# Digit.net
KiCad netlist of a schematic drawn in Altium Designer
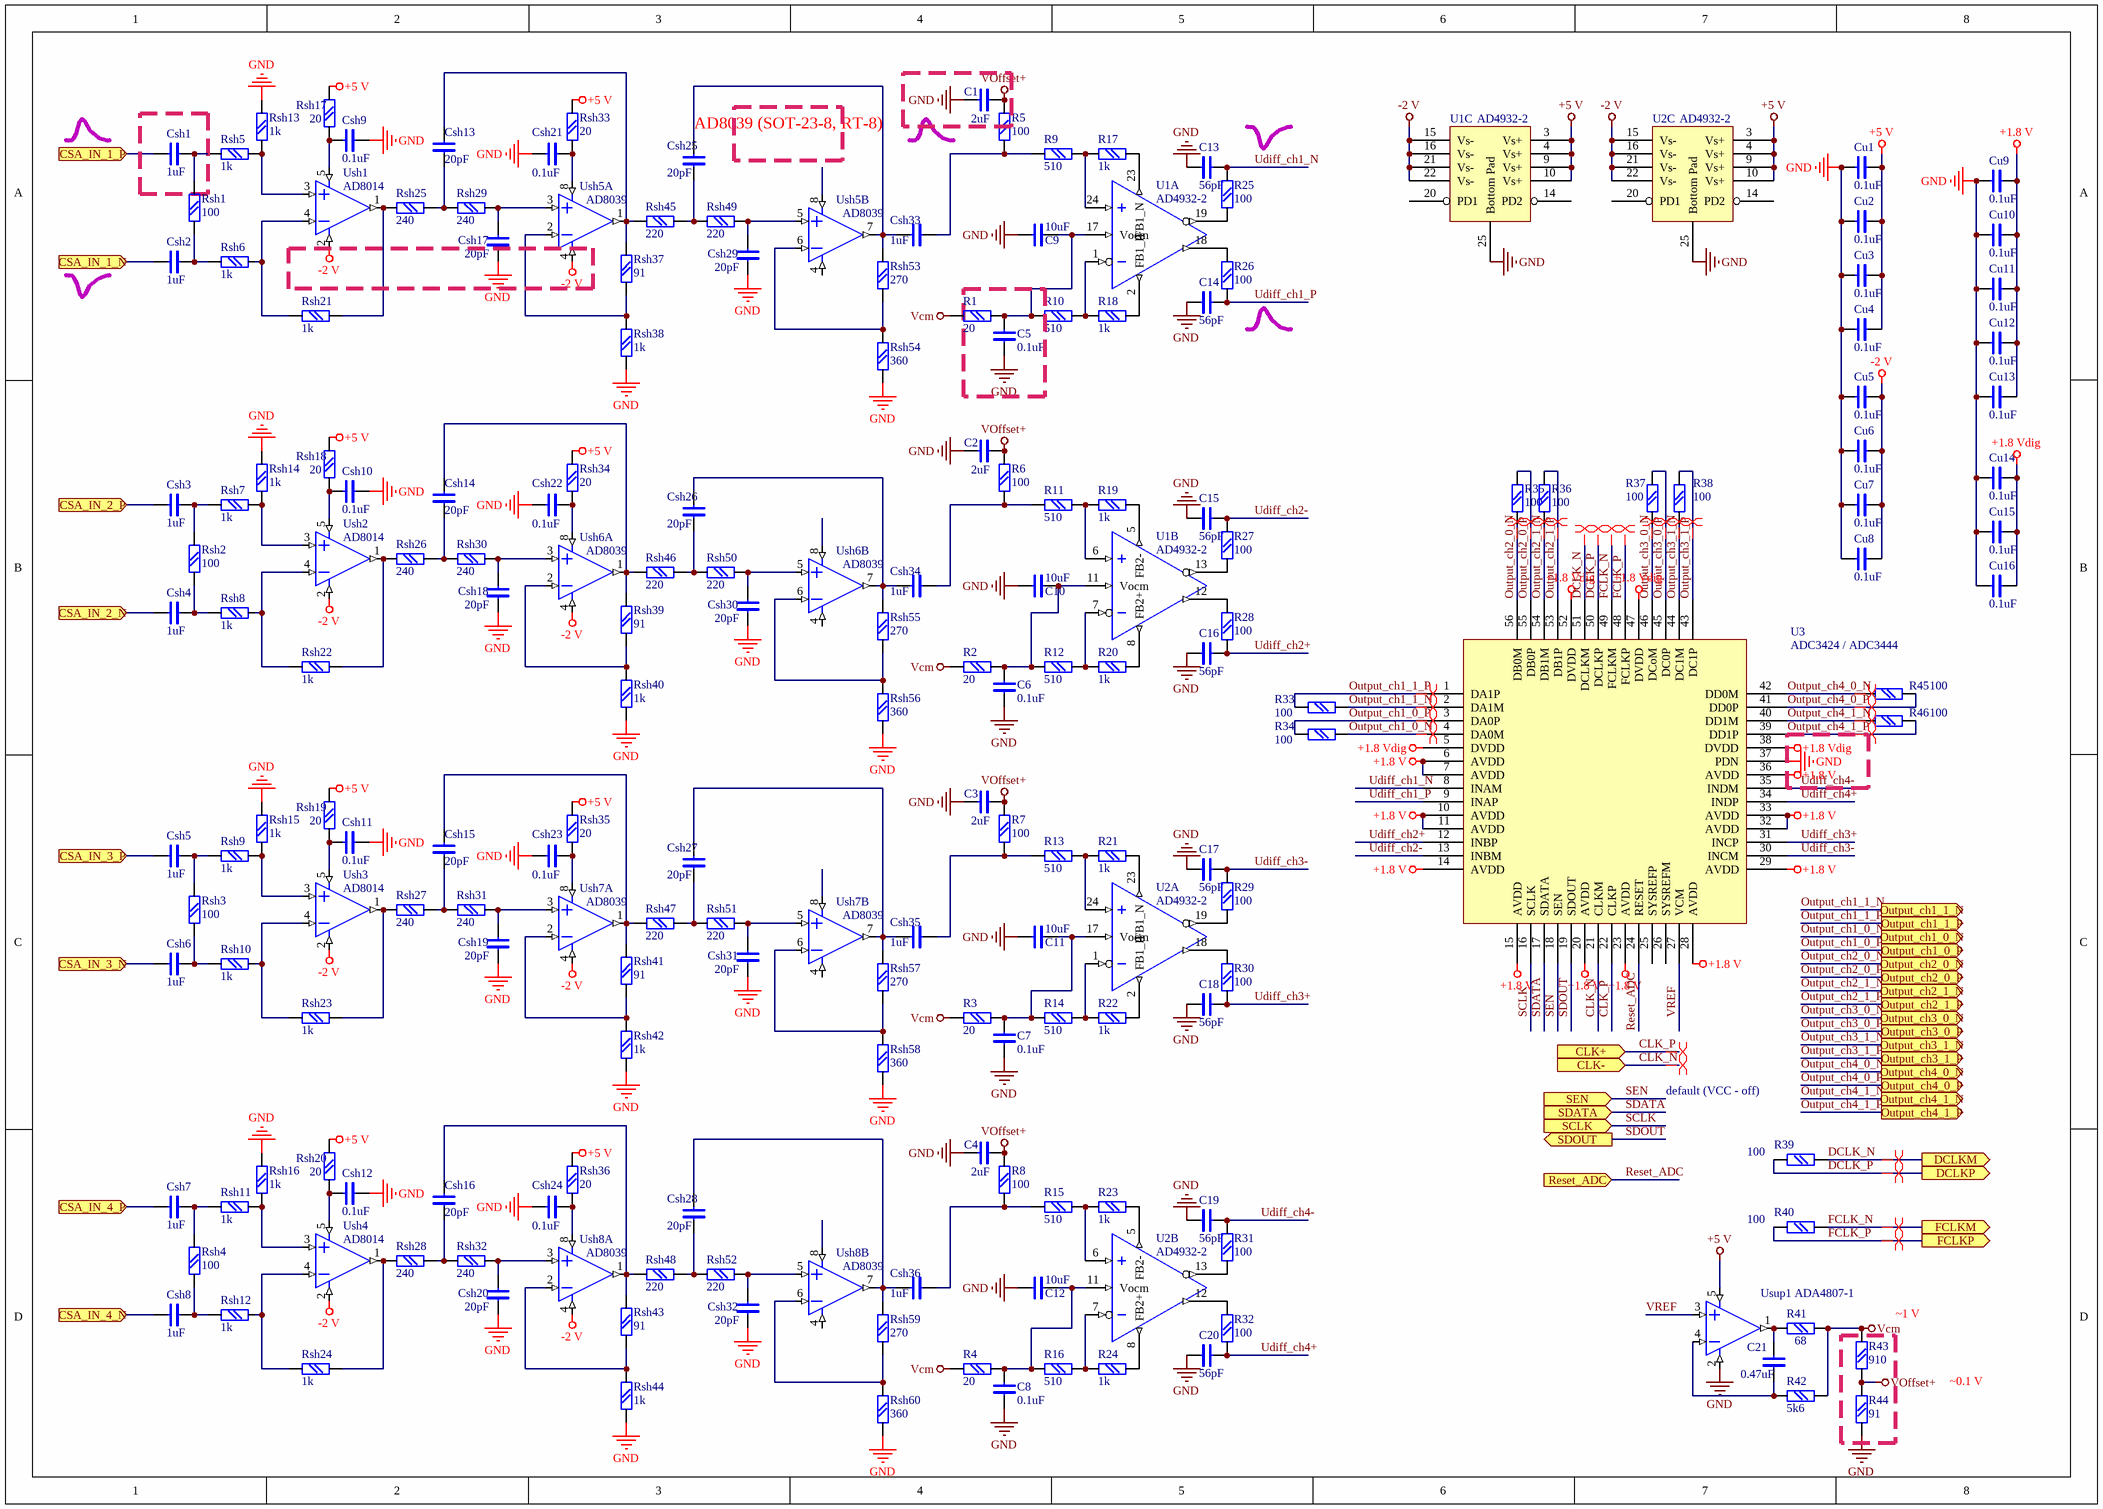
[diagram p0: Digit.SchDoc]

(export (version "E")
  (design (tool "Eeschema 10.0.6"))
  (components
    (comp (ref "C1") (value "2uF") (footprint "chip0603") (libsource (lib "vDevice") (part "C")))
    (comp (ref "C2") (value "2uF") (footprint "chip0603") (libsource (lib "vDevice") (part "C")))
    (comp (ref "C3") (value "2uF") (footprint "chip0603") (libsource (lib "vDevice") (part "C")))
    (comp (ref "C4") (value "2uF") (footprint "chip0603") (libsource (lib "vDevice") (part "C")))
    (comp (ref "C5") (value "0.1uF") (footprint "chip0603") (libsource (lib "vDevice") (part "C")))
    (comp (ref "C6") (value "0.1uF") (footprint "chip0603") (libsource (lib "vDevice") (part "C")))
    (comp (ref "C7") (value "0.1uF") (footprint "chip0603") (libsource (lib "vDevice") (part "C")))
    (comp (ref "C8") (value "0.1uF") (footprint "chip0603") (libsource (lib "vDevice") (part "C")))
    (comp (ref "C9") (value "10uF") (footprint "chip0603") (libsource (lib "vDevice") (part "C")))
    (comp (ref "C10") (value "10uF") (footprint "chip0603") (libsource (lib "vDevice") (part "C")))
    (comp (ref "C11") (value "10uF") (footprint "chip0603") (libsource (lib "vDevice") (part "C")))
    (comp (ref "C12") (value "10uF") (footprint "chip0603") (libsource (lib "vDevice") (part "C")))
    (comp (ref "C13") (value "56pF") (footprint "chip0603") (libsource (lib "vDevice") (part "C")))
    (comp (ref "C14") (value "56pF") (footprint "chip0603") (libsource (lib "vDevice") (part "C")))
    (comp (ref "C15") (value "56pF") (footprint "chip0603") (libsource (lib "vDevice") (part "C")))
    (comp (ref "C16") (value "56pF") (footprint "chip0603") (libsource (lib "vDevice") (part "C")))
    (comp (ref "C17") (value "56pF") (footprint "chip0603") (libsource (lib "vDevice") (part "C")))
    (comp (ref "C18") (value "56pF") (footprint "chip0603") (libsource (lib "vDevice") (part "C")))
    (comp (ref "C19") (value "56pF") (footprint "chip0603") (libsource (lib "vDevice") (part "C")))
    (comp (ref "C20") (value "56pF") (footprint "chip0603") (libsource (lib "vDevice") (part "C")))
    (comp (ref "C21") (value "0.47uF") (footprint "chip0603") (libsource (lib "*") (part "C")))
    (comp (ref "Csh1") (value "1uF") (footprint "chip0603") (libsource (lib "*") (part "C")))
    (comp (ref "Csh2") (value "1uF") (footprint "chip0603") (libsource (lib "*") (part "C")))
    (comp (ref "Csh3") (value "1uF") (footprint "chip0603") (libsource (lib "*") (part "C")))
    (comp (ref "Csh4") (value "1uF") (footprint "chip0603") (libsource (lib "*") (part "C")))
    (comp (ref "Csh5") (value "1uF") (footprint "chip0603") (libsource (lib "*") (part "C")))
    (comp (ref "Csh6") (value "1uF") (footprint "chip0603") (libsource (lib "*") (part "C")))
    (comp (ref "Csh7") (value "1uF") (footprint "chip0603") (libsource (lib "*") (part "C")))
    (comp (ref "Csh8") (value "1uF") (footprint "chip0603") (libsource (lib "*") (part "C")))
    (comp (ref "Csh9") (value "0.1uF") (footprint "chip0603") (libsource (lib "*") (part "C")))
    (comp (ref "Csh10") (value "0.1uF") (footprint "chip0603") (libsource (lib "*") (part "C")))
    (comp (ref "Csh11") (value "0.1uF") (footprint "chip0603") (libsource (lib "*") (part "C")))
    (comp (ref "Csh12") (value "0.1uF") (footprint "chip0603") (libsource (lib "*") (part "C")))
    (comp (ref "Csh13") (value "20pF") (footprint "chip0603") (libsource (lib "*") (part "C")))
    (comp (ref "Csh14") (value "20pF") (footprint "chip0603") (libsource (lib "*") (part "C")))
    (comp (ref "Csh15") (value "20pF") (footprint "chip0603") (libsource (lib "*") (part "C")))
    (comp (ref "Csh16") (value "20pF") (footprint "chip0603") (libsource (lib "*") (part "C")))
    (comp (ref "Csh17") (value "20pF") (footprint "chip0603") (libsource (lib "*") (part "C")))
    (comp (ref "Csh18") (value "20pF") (footprint "chip0603") (libsource (lib "*") (part "C")))
    (comp (ref "Csh19") (value "20pF") (footprint "chip0603") (libsource (lib "*") (part "C")))
    (comp (ref "Csh20") (value "20pF") (footprint "chip0603") (libsource (lib "*") (part "C")))
    (comp (ref "Csh21") (value "0.1uF") (footprint "chip0603") (libsource (lib "*") (part "C")))
    (comp (ref "Csh22") (value "0.1uF") (footprint "chip0603") (libsource (lib "*") (part "C")))
    (comp (ref "Csh23") (value "0.1uF") (footprint "chip0603") (libsource (lib "*") (part "C")))
    (comp (ref "Csh24") (value "0.1uF") (footprint "chip0603") (libsource (lib "*") (part "C")))
    (comp (ref "Csh25") (value "20pF") (footprint "chip0603") (libsource (lib "*") (part "C")))
    (comp (ref "Csh26") (value "20pF") (footprint "chip0603") (libsource (lib "*") (part "C")))
    (comp (ref "Csh27") (value "20pF") (footprint "chip0603") (libsource (lib "*") (part "C")))
    (comp (ref "Csh28") (value "20pF") (footprint "chip0603") (libsource (lib "*") (part "C")))
    (comp (ref "Csh29") (value "20pF") (footprint "chip0603") (libsource (lib "*") (part "C")))
    (comp (ref "Csh30") (value "20pF") (footprint "chip0603") (libsource (lib "*") (part "C")))
    (comp (ref "Csh31") (value "20pF") (footprint "chip0603") (libsource (lib "*") (part "C")))
    (comp (ref "Csh32") (value "20pF") (footprint "chip0603") (libsource (lib "*") (part "C")))
    (comp (ref "Csh33") (value "1uF") (footprint "chip0603") (libsource (lib "*") (part "C")))
    (comp (ref "Csh34") (value "1uF") (footprint "chip0603") (libsource (lib "*") (part "C")))
    (comp (ref "Csh35") (value "1uF") (footprint "chip0603") (libsource (lib "*") (part "C")))
    (comp (ref "Csh36") (value "1uF") (footprint "chip0603") (libsource (lib "*") (part "C")))
    (comp (ref "Cu1") (value "0.1uF") (footprint "chip0603") (libsource (lib "*") (part "C")))
    (comp (ref "Cu2") (value "0.1uF") (footprint "chip0603") (libsource (lib "*") (part "C")))
    (comp (ref "Cu3") (value "0.1uF") (footprint "chip0603") (libsource (lib "*") (part "C")))
    (comp (ref "Cu4") (value "0.1uF") (footprint "chip0603") (libsource (lib "*") (part "C")))
    (comp (ref "Cu5") (value "0.1uF") (footprint "chip0603") (libsource (lib "*") (part "C")))
    (comp (ref "Cu6") (value "0.1uF") (footprint "chip0603") (libsource (lib "*") (part "C")))
    (comp (ref "Cu7") (value "0.1uF") (footprint "chip0603") (libsource (lib "*") (part "C")))
    (comp (ref "Cu8") (value "0.1uF") (footprint "chip0603") (libsource (lib "*") (part "C")))
    (comp (ref "Cu9") (value "0.1uF") (footprint "chip0603") (libsource (lib "*") (part "C")))
    (comp (ref "Cu10") (value "0.1uF") (footprint "chip0603") (libsource (lib "*") (part "C")))
    (comp (ref "Cu11") (value "0.1uF") (footprint "chip0603") (libsource (lib "*") (part "C")))
    (comp (ref "Cu12") (value "0.1uF") (footprint "chip0603") (libsource (lib "*") (part "C")))
    (comp (ref "Cu13") (value "0.1uF") (footprint "chip0603") (libsource (lib "*") (part "C")))
    (comp (ref "Cu14") (value "0.1uF") (footprint "chip0603") (libsource (lib "*") (part "C")))
    (comp (ref "Cu15") (value "0.1uF") (footprint "chip0603") (libsource (lib "*") (part "C")))
    (comp (ref "Cu16") (value "0.1uF") (footprint "chip0603") (libsource (lib "*") (part "C")))
    (comp (ref "R1") (value "20") (footprint "chip0603") (libsource (lib "vDevice") (part "R")))
    (comp (ref "R2") (value "20") (footprint "chip0603") (libsource (lib "vDevice") (part "R")))
    (comp (ref "R3") (value "20") (footprint "chip0603") (libsource (lib "vDevice") (part "R")))
    (comp (ref "R4") (value "20") (footprint "chip0603") (libsource (lib "vDevice") (part "R")))
    (comp (ref "R5") (value "100") (footprint "chip0603") (libsource (lib "vDevice") (part "R")))
    (comp (ref "R6") (value "100") (footprint "chip0603") (libsource (lib "vDevice") (part "R")))
    (comp (ref "R7") (value "100") (footprint "chip0603") (libsource (lib "vDevice") (part "R")))
    (comp (ref "R8") (value "100") (footprint "chip0603") (libsource (lib "vDevice") (part "R")))
    (comp (ref "R9") (value "510") (footprint "chip0603") (libsource (lib "vDevice") (part "R")))
    (comp (ref "R10") (value "510") (footprint "chip0603") (libsource (lib "vDevice") (part "R")))
    (comp (ref "R11") (value "510") (footprint "chip0603") (libsource (lib "vDevice") (part "R")))
    (comp (ref "R12") (value "510") (footprint "chip0603") (libsource (lib "vDevice") (part "R")))
    (comp (ref "R13") (value "510") (footprint "chip0603") (libsource (lib "vDevice") (part "R")))
    (comp (ref "R14") (value "510") (footprint "chip0603") (libsource (lib "vDevice") (part "R")))
    (comp (ref "R15") (value "510") (footprint "chip0603") (libsource (lib "vDevice") (part "R")))
    (comp (ref "R16") (value "510") (footprint "chip0603") (libsource (lib "vDevice") (part "R")))
    (comp (ref "R17") (value "1k") (footprint "chip0603") (libsource (lib "vDevice") (part "R")))
    (comp (ref "R18") (value "1k") (footprint "chip0603") (libsource (lib "vDevice") (part "R")))
    (comp (ref "R19") (value "1k") (footprint "chip0603") (libsource (lib "vDevice") (part "R")))
    (comp (ref "R20") (value "1k") (footprint "chip0603") (libsource (lib "vDevice") (part "R")))
    (comp (ref "R21") (value "1k") (footprint "chip0603") (libsource (lib "vDevice") (part "R")))
    (comp (ref "R22") (value "1k") (footprint "chip0603") (libsource (lib "vDevice") (part "R")))
    (comp (ref "R23") (value "1k") (footprint "chip0603") (libsource (lib "vDevice") (part "R")))
    (comp (ref "R24") (value "1k") (footprint "chip0603") (libsource (lib "vDevice") (part "R")))
    (comp (ref "R25") (value "100") (footprint "chip0603") (libsource (lib "vDevice") (part "R")))
    (comp (ref "R26") (value "100") (footprint "chip0603") (libsource (lib "vDevice") (part "R")))
    (comp (ref "R27") (value "100") (footprint "chip0603") (libsource (lib "vDevice") (part "R")))
    (comp (ref "R28") (value "100") (footprint "chip0603") (libsource (lib "vDevice") (part "R")))
    (comp (ref "R29") (value "100") (footprint "chip0603") (libsource (lib "vDevice") (part "R")))
    (comp (ref "R30") (value "100") (footprint "chip0603") (libsource (lib "vDevice") (part "R")))
    (comp (ref "R31") (value "100") (footprint "chip0603") (libsource (lib "vDevice") (part "R")))
    (comp (ref "R32") (value "100") (footprint "chip0603") (libsource (lib "vDevice") (part "R")))
    (comp (ref "R33") (value "100") (footprint "0402") (libsource (lib "vDevice") (part "R")))
    (comp (ref "R34") (value "100") (footprint "0402") (libsource (lib "vDevice") (part "R")))
    (comp (ref "R35") (value "100") (footprint "0402") (libsource (lib "vDevice") (part "R")))
    (comp (ref "R36") (value "100") (footprint "0402") (libsource (lib "vDevice") (part "R")))
    (comp (ref "R37") (value "100") (footprint "0402") (libsource (lib "vDevice") (part "R")))
    (comp (ref "R38") (value "100") (footprint "0402") (libsource (lib "vDevice") (part "R")))
    (comp (ref "R39") (value "100") (footprint "0402") (libsource (lib "vDevice") (part "R")))
    (comp (ref "R40") (value "100") (footprint "0402") (libsource (lib "vDevice") (part "R")))
    (comp (ref "R41") (value "68") (footprint "chip0603") (libsource (lib "vDevice") (part "R")))
    (comp (ref "R42") (value "5k6") (footprint "chip0603") (libsource (lib "vDevice") (part "R")))
    (comp (ref "R43") (value "910") (footprint "chip0603") (libsource (lib "vDevice") (part "R")))
    (comp (ref "R44") (value "91") (footprint "chip0603") (libsource (lib "vDevice") (part "R")))
    (comp (ref "R45") (value "100") (footprint "0402") (libsource (lib "vDevice") (part "R")))
    (comp (ref "R46") (value "100") (footprint "0402") (libsource (lib "vDevice") (part "R")))
    (comp (ref "Rsh1") (value "100") (footprint "chip0603") (libsource (lib "vDevice") (part "R")))
    (comp (ref "Rsh2") (value "100") (footprint "chip0603") (libsource (lib "vDevice") (part "R")))
    (comp (ref "Rsh3") (value "100") (footprint "chip0603") (libsource (lib "vDevice") (part "R")))
    (comp (ref "Rsh4") (value "100") (footprint "chip0603") (libsource (lib "vDevice") (part "R")))
    (comp (ref "Rsh5") (value "1k") (footprint "chip0603") (libsource (lib "vDevice") (part "R")))
    (comp (ref "Rsh6") (value "1k") (footprint "chip0603") (libsource (lib "vDevice") (part "R")))
    (comp (ref "Rsh7") (value "1k") (footprint "chip0603") (libsource (lib "vDevice") (part "R")))
    (comp (ref "Rsh8") (value "1k") (footprint "chip0603") (libsource (lib "vDevice") (part "R")))
    (comp (ref "Rsh9") (value "1k") (footprint "chip0603") (libsource (lib "vDevice") (part "R")))
    (comp (ref "Rsh10") (value "1k") (footprint "chip0603") (libsource (lib "vDevice") (part "R")))
    (comp (ref "Rsh11") (value "1k") (footprint "chip0603") (libsource (lib "vDevice") (part "R")))
    (comp (ref "Rsh12") (value "1k") (footprint "chip0603") (libsource (lib "vDevice") (part "R")))
    (comp (ref "Rsh13") (value "1k") (footprint "chip0603") (libsource (lib "vDevice") (part "R")))
    (comp (ref "Rsh14") (value "1k") (footprint "chip0603") (libsource (lib "vDevice") (part "R")))
    (comp (ref "Rsh15") (value "1k") (footprint "chip0603") (libsource (lib "vDevice") (part "R")))
    (comp (ref "Rsh16") (value "1k") (footprint "chip0603") (libsource (lib "vDevice") (part "R")))
    (comp (ref "Rsh17") (value "20") (footprint "chip0603") (libsource (lib "*") (part "R")))
    (comp (ref "Rsh18") (value "20") (footprint "chip0603") (libsource (lib "*") (part "R")))
    (comp (ref "Rsh19") (value "20") (footprint "chip0603") (libsource (lib "*") (part "R")))
    (comp (ref "Rsh20") (value "20") (footprint "chip0603") (libsource (lib "*") (part "R")))
    (comp (ref "Rsh21") (value "1k") (footprint "chip0603") (libsource (lib "vDevice") (part "R")))
    (comp (ref "Rsh22") (value "1k") (footprint "chip0603") (libsource (lib "vDevice") (part "R")))
    (comp (ref "Rsh23") (value "1k") (footprint "chip0603") (libsource (lib "vDevice") (part "R")))
    (comp (ref "Rsh24") (value "1k") (footprint "chip0603") (libsource (lib "vDevice") (part "R")))
    (comp (ref "Rsh25") (value "240") (footprint "chip0603") (libsource (lib "vDevice") (part "R")))
    (comp (ref "Rsh26") (value "240") (footprint "chip0603") (libsource (lib "vDevice") (part "R")))
    (comp (ref "Rsh27") (value "240") (footprint "chip0603") (libsource (lib "vDevice") (part "R")))
    (comp (ref "Rsh28") (value "240") (footprint "chip0603") (libsource (lib "vDevice") (part "R")))
    (comp (ref "Rsh29") (value "240") (footprint "chip0603") (libsource (lib "vDevice") (part "R")))
    (comp (ref "Rsh30") (value "240") (footprint "chip0603") (libsource (lib "vDevice") (part "R")))
    (comp (ref "Rsh31") (value "240") (footprint "chip0603") (libsource (lib "vDevice") (part "R")))
    (comp (ref "Rsh32") (value "240") (footprint "chip0603") (libsource (lib "vDevice") (part "R")))
    (comp (ref "Rsh33") (value "20") (footprint "chip0603") (libsource (lib "*") (part "R")))
    (comp (ref "Rsh34") (value "20") (footprint "chip0603") (libsource (lib "*") (part "R")))
    (comp (ref "Rsh35") (value "20") (footprint "chip0603") (libsource (lib "*") (part "R")))
    (comp (ref "Rsh36") (value "20") (footprint "chip0603") (libsource (lib "*") (part "R")))
    (comp (ref "Rsh37") (value "91") (footprint "chip0603") (libsource (lib "vDevice") (part "R")))
    (comp (ref "Rsh38") (value "1k") (footprint "chip0603") (libsource (lib "vDevice") (part "R")))
    (comp (ref "Rsh39") (value "91") (footprint "chip0603") (libsource (lib "vDevice") (part "R")))
    (comp (ref "Rsh40") (value "1k") (footprint "chip0603") (libsource (lib "vDevice") (part "R")))
    (comp (ref "Rsh41") (value "91") (footprint "chip0603") (libsource (lib "vDevice") (part "R")))
    (comp (ref "Rsh42") (value "1k") (footprint "chip0603") (libsource (lib "vDevice") (part "R")))
    (comp (ref "Rsh43") (value "91") (footprint "chip0603") (libsource (lib "vDevice") (part "R")))
    (comp (ref "Rsh44") (value "1k") (footprint "chip0603") (libsource (lib "vDevice") (part "R")))
    (comp (ref "Rsh45") (value "220") (footprint "chip0603") (libsource (lib "vDevice") (part "R")))
    (comp (ref "Rsh46") (value "220") (footprint "chip0603") (libsource (lib "vDevice") (part "R")))
    (comp (ref "Rsh47") (value "220") (footprint "chip0603") (libsource (lib "vDevice") (part "R")))
    (comp (ref "Rsh48") (value "220") (footprint "chip0603") (libsource (lib "vDevice") (part "R")))
    (comp (ref "Rsh49") (value "220") (footprint "chip0603") (libsource (lib "vDevice") (part "R")))
    (comp (ref "Rsh50") (value "220") (footprint "chip0603") (libsource (lib "vDevice") (part "R")))
    (comp (ref "Rsh51") (value "220") (footprint "chip0603") (libsource (lib "vDevice") (part "R")))
    (comp (ref "Rsh52") (value "220") (footprint "chip0603") (libsource (lib "vDevice") (part "R")))
    (comp (ref "Rsh53") (value "270") (footprint "chip0603") (libsource (lib "vDevice") (part "R")))
    (comp (ref "Rsh54") (value "360") (footprint "chip0603") (libsource (lib "vDevice") (part "R")))
    (comp (ref "Rsh55") (value "270") (footprint "chip0603") (libsource (lib "vDevice") (part "R")))
    (comp (ref "Rsh56") (value "360") (footprint "chip0603") (libsource (lib "vDevice") (part "R")))
    (comp (ref "Rsh57") (value "270") (footprint "chip0603") (libsource (lib "vDevice") (part "R")))
    (comp (ref "Rsh58") (value "360") (footprint "chip0603") (libsource (lib "vDevice") (part "R")))
    (comp (ref "Rsh59") (value "270") (footprint "chip0603") (libsource (lib "vDevice") (part "R")))
    (comp (ref "Rsh60") (value "360") (footprint "chip0603") (libsource (lib "vDevice") (part "R")))
    (comp (ref "U1") (value "AD4932-2") (footprint "CP-24-13") (libsource (lib "") (part "AD4932-2_1")))
    (comp (ref "U2") (value "AD4932-2") (footprint "CP-24-13") (libsource (lib "") (part "AD4932-2_1")))
    (comp (ref "U3")
      (value "ADC3424 / ADC3444")
      (footprint "PQFN-56")
      (libsource (lib "Backup of Mylib") (part "ADC3424"))
    )
    (comp (ref "Ush1") (value "AD8014") (footprint "RT-5") (libsource (lib "vAnalog") (part "AD8005ART")))
    (comp (ref "Ush2") (value "AD8014") (footprint "RT-5") (libsource (lib "vAnalog") (part "AD8005ART")))
    (comp (ref "Ush3") (value "AD8014") (footprint "RT-5") (libsource (lib "vAnalog") (part "AD8005ART")))
    (comp (ref "Ush4") (value "AD8014") (footprint "RT-5") (libsource (lib "vAnalog") (part "AD8005ART")))
    (comp (ref "Ush5") (value "AD8039") (footprint "SOT23-8") (libsource (lib "vAnalog") (part "AD8008")))
    (comp (ref "Ush6") (value "AD8039") (footprint "SOT23-8") (libsource (lib "vAnalog") (part "AD8008")))
    (comp (ref "Ush7") (value "AD8039") (footprint "SOT23-8") (libsource (lib "vAnalog") (part "AD8008")))
    (comp (ref "Ush8") (value "AD8039") (footprint "SOT23-8") (libsource (lib "vAnalog") (part "AD8008")))
    (comp (ref "Usup1")
      (value "ADA4807-1")
      (footprint "SOT23-5")
      (libsource (lib "vAnalog") (part "AD8005ART"))
    )
  )
  (nets
    (net (code "1") (name "+1.8 V") (class "Default")
      (node (ref "Cu10") (pin "2") (pinfunction "2_2") (pintype "passive"))
      (node (ref "Cu11") (pin "2") (pinfunction "2_2") (pintype "passive"))
      (node (ref "Cu12") (pin "2") (pinfunction "2_2") (pintype "passive"))
      (node (ref "Cu13") (pin "2") (pinfunction "2_2") (pintype "passive"))
      (node (ref "Cu9") (pin "2") (pinfunction "2_2") (pintype "passive"))
      (node (ref "U3") (pin "10") (pinfunction "AVDD_10") (pintype "passive"))
      (node (ref "U3") (pin "11") (pinfunction "AVDD_11") (pintype "passive"))
      (node (ref "U3") (pin "14") (pinfunction "AVDD_14") (pintype "passive"))
      (node (ref "U3") (pin "15") (pinfunction "AVDD_15") (pintype "passive"))
      (node (ref "U3") (pin "20") (pinfunction "AVDD_20") (pintype "passive"))
      (node (ref "U3") (pin "23") (pinfunction "AVDD_23") (pintype "passive"))
      (node (ref "U3") (pin "28") (pinfunction "AVDD_28") (pintype "passive"))
      (node (ref "U3") (pin "29") (pinfunction "AVDD_29") (pintype "passive"))
      (node (ref "U3") (pin "32") (pinfunction "AVDD_32") (pintype "passive"))
      (node (ref "U3") (pin "33") (pinfunction "AVDD_33") (pintype "passive"))
      (node (ref "U3") (pin "36") (pinfunction "AVDD_36") (pintype "passive"))
      (node (ref "U3") (pin "6") (pinfunction "AVDD_6") (pintype "passive"))
      (node (ref "U3") (pin "7") (pinfunction "AVDD_7") (pintype "passive"))
    )
    (net (code "2") (name "+1.8 Vdig") (class "Default")
      (node (ref "Cu14") (pin "2") (pinfunction "2_2") (pintype "passive"))
      (node (ref "Cu15") (pin "2") (pinfunction "2_2") (pintype "passive"))
      (node (ref "Cu16") (pin "2") (pinfunction "2_2") (pintype "passive"))
      (node (ref "U3") (pin "38") (pinfunction "DVDD_38") (pintype "passive"))
      (node (ref "U3") (pin "47") (pinfunction "DVDD_47") (pintype "passive"))
      (node (ref "U3") (pin "5") (pinfunction "DVDD_5") (pintype "passive"))
      (node (ref "U3") (pin "52") (pinfunction "DVDD_52") (pintype "passive"))
    )
    (net (code "3") (name "+5 V") (class "Default")
      (node (ref "Cu1") (pin "2") (pinfunction "2_2") (pintype "passive"))
      (node (ref "Cu2") (pin "2") (pinfunction "2_2") (pintype "passive"))
      (node (ref "Cu3") (pin "2") (pinfunction "2_2") (pintype "passive"))
      (node (ref "Cu4") (pin "2") (pinfunction "2_2") (pintype "passive"))
      (node (ref "Rsh17") (pin "2") (pinfunction "2_2") (pintype "passive"))
      (node (ref "Rsh18") (pin "2") (pinfunction "2_2") (pintype "passive"))
      (node (ref "Rsh19") (pin "2") (pinfunction "2_2") (pintype "passive"))
      (node (ref "Rsh20") (pin "2") (pinfunction "2_2") (pintype "passive"))
      (node (ref "Rsh33") (pin "2") (pinfunction "2_2") (pintype "passive"))
      (node (ref "Rsh34") (pin "2") (pinfunction "2_2") (pintype "passive"))
      (node (ref "Rsh35") (pin "2") (pinfunction "2_2") (pintype "passive"))
      (node (ref "Rsh36") (pin "2") (pinfunction "2_2") (pintype "passive"))
      (node (ref "U1") (pin "10") (pinfunction "Vs+_10") (pintype "power_in"))
      (node (ref "U1") (pin "3") (pinfunction "Vs+_3") (pintype "power_in"))
      (node (ref "U1") (pin "4") (pinfunction "Vs+_4") (pintype "power_in"))
      (node (ref "U1") (pin "9") (pinfunction "Vs+_9") (pintype "power_in"))
      (node (ref "U2") (pin "10") (pinfunction "Vs+_10") (pintype "power_in"))
      (node (ref "U2") (pin "3") (pinfunction "Vs+_3") (pintype "power_in"))
      (node (ref "U2") (pin "4") (pinfunction "Vs+_4") (pintype "power_in"))
      (node (ref "U2") (pin "9") (pinfunction "Vs+_9") (pintype "power_in"))
      (node (ref "Usup1") (pin "5") (pinfunction "E+_5") (pintype "input"))
    )
    (net (code "4") (name "-2 V") (class "Default")
      (node (ref "Cu5") (pin "2") (pinfunction "2_2") (pintype "passive"))
      (node (ref "Cu6") (pin "2") (pinfunction "2_2") (pintype "passive"))
      (node (ref "Cu7") (pin "2") (pinfunction "2_2") (pintype "passive"))
      (node (ref "Cu8") (pin "2") (pinfunction "2_2") (pintype "passive"))
      (node (ref "U1") (pin "15") (pinfunction "Vs-_15") (pintype "power_in"))
      (node (ref "U1") (pin "16") (pinfunction "Vs-_16") (pintype "power_in"))
      (node (ref "U1") (pin "21") (pinfunction "Vs-_21") (pintype "power_in"))
      (node (ref "U1") (pin "22") (pinfunction "Vs-_22") (pintype "power_in"))
      (node (ref "U2") (pin "15") (pinfunction "Vs-_15") (pintype "power_in"))
      (node (ref "U2") (pin "16") (pinfunction "Vs-_16") (pintype "power_in"))
      (node (ref "U2") (pin "21") (pinfunction "Vs-_21") (pintype "power_in"))
      (node (ref "U2") (pin "22") (pinfunction "Vs-_22") (pintype "power_in"))
      (node (ref "Ush1") (pin "2") (pinfunction "E-_2") (pintype "input"))
      (node (ref "Ush2") (pin "2") (pinfunction "E-_2") (pintype "input"))
      (node (ref "Ush3") (pin "2") (pinfunction "E-_2") (pintype "input"))
      (node (ref "Ush4") (pin "2") (pinfunction "E-_2") (pintype "input"))
      (node (ref "Ush5") (pin "4") (pinfunction "E-_4") (pintype "input"))
      (node (ref "Ush6") (pin "4") (pinfunction "E-_4") (pintype "input"))
      (node (ref "Ush7") (pin "4") (pinfunction "E-_4") (pintype "input"))
      (node (ref "Ush8") (pin "4") (pinfunction "E-_4") (pintype "input"))
    )
    (net (code "5") (name "/CLK_N") (class "Default")
      (node (ref "U3") (pin "21") (pinfunction "CLKM_21") (pintype "passive"))
    )
    (net (code "6") (name "/CLK_P") (class "Default")
      (node (ref "U3") (pin "22") (pinfunction "CLKP_22") (pintype "passive"))
    )
    (net (code "7") (name "/CSA_IN_1_N") (class "Default")
      (node (ref "Csh2") (pin "1") (pinfunction "1_1") (pintype "passive"))
    )
    (net (code "8") (name "/CSA_IN_1_P") (class "Default")
      (node (ref "Csh1") (pin "1") (pinfunction "1_1") (pintype "passive"))
    )
    (net (code "9") (name "/CSA_IN_2_N") (class "Default")
      (node (ref "Csh4") (pin "1") (pinfunction "1_1") (pintype "passive"))
    )
    (net (code "10") (name "/CSA_IN_2_P") (class "Default")
      (node (ref "Csh3") (pin "1") (pinfunction "1_1") (pintype "passive"))
    )
    (net (code "11") (name "/CSA_IN_3_N") (class "Default")
      (node (ref "Csh6") (pin "1") (pinfunction "1_1") (pintype "passive"))
    )
    (net (code "12") (name "/CSA_IN_3_P") (class "Default")
      (node (ref "Csh5") (pin "1") (pinfunction "1_1") (pintype "passive"))
    )
    (net (code "13") (name "/CSA_IN_4_N") (class "Default")
      (node (ref "Csh8") (pin "1") (pinfunction "1_1") (pintype "passive"))
    )
    (net (code "14") (name "/CSA_IN_4_P") (class "Default")
      (node (ref "Csh7") (pin "1") (pinfunction "1_1") (pintype "passive"))
    )
    (net (code "15") (name "/DCLK_N") (class "Default")
      (node (ref "R39") (pin "2") (pinfunction "2_2") (pintype "passive"))
      (node (ref "U3") (pin "51") (pinfunction "DCLKM_51") (pintype "passive"))
    )
    (net (code "16") (name "/DCLK_P") (class "Default")
      (node (ref "R39") (pin "1") (pinfunction "1_1") (pintype "passive"))
      (node (ref "U3") (pin "50") (pinfunction "DCLKP_50") (pintype "passive"))
    )
    (net (code "17") (name "/FCLK_N") (class "Default")
      (node (ref "R40") (pin "2") (pinfunction "2_2") (pintype "passive"))
      (node (ref "U3") (pin "49") (pinfunction "FCLKM_49") (pintype "passive"))
    )
    (net (code "18") (name "/FCLK_P") (class "Default")
      (node (ref "R40") (pin "1") (pinfunction "1_1") (pintype "passive"))
      (node (ref "U3") (pin "48") (pinfunction "FCLKP_48") (pintype "passive"))
    )
    (net (code "19") (name "/Output_ch1_0_N") (class "Default")
      (node (ref "R34") (pin "2") (pinfunction "2_2") (pintype "passive"))
      (node (ref "U3") (pin "4") (pinfunction "DA0M_4") (pintype "passive"))
    )
    (net (code "20") (name "/Output_ch1_0_P") (class "Default")
      (node (ref "R34") (pin "1") (pinfunction "1_1") (pintype "passive"))
      (node (ref "U3") (pin "3") (pinfunction "DA0P_3") (pintype "passive"))
    )
    (net (code "21") (name "/Output_ch1_1_N") (class "Default")
      (node (ref "R33") (pin "2") (pinfunction "2_2") (pintype "passive"))
      (node (ref "U3") (pin "2") (pinfunction "DA1M_2") (pintype "passive"))
    )
    (net (code "22") (name "/Output_ch1_1_P") (class "Default")
      (node (ref "R33") (pin "1") (pinfunction "1_1") (pintype "passive"))
      (node (ref "U3") (pin "1") (pinfunction "DA1P_1") (pintype "passive"))
    )
    (net (code "23") (name "/Output_ch2_0_N") (class "Default")
      (node (ref "R35") (pin "1") (pinfunction "1_1") (pintype "passive"))
      (node (ref "U3") (pin "56") (pinfunction "DB0M_56") (pintype "passive"))
    )
    (net (code "24") (name "/Output_ch2_0_P") (class "Default")
      (node (ref "R35") (pin "2") (pinfunction "2_2") (pintype "passive"))
      (node (ref "U3") (pin "55") (pinfunction "DB0P_55") (pintype "passive"))
    )
    (net (code "25") (name "/Output_ch2_1_N") (class "Default")
      (node (ref "R36") (pin "1") (pinfunction "1_1") (pintype "passive"))
      (node (ref "U3") (pin "54") (pinfunction "DB1M_54") (pintype "passive"))
    )
    (net (code "26") (name "/Output_ch2_1_P") (class "Default")
      (node (ref "R36") (pin "2") (pinfunction "2_2") (pintype "passive"))
      (node (ref "U3") (pin "53") (pinfunction "DB1P_53") (pintype "passive"))
    )
    (net (code "27") (name "/Output_ch3_0_N") (class "Default")
      (node (ref "R37") (pin "1") (pinfunction "1_1") (pintype "passive"))
      (node (ref "U3") (pin "46") (pinfunction "DCoM_46") (pintype "passive"))
    )
    (net (code "28") (name "/Output_ch3_0_P") (class "Default")
      (node (ref "R37") (pin "2") (pinfunction "2_2") (pintype "passive"))
      (node (ref "U3") (pin "45") (pinfunction "DC0P_45") (pintype "passive"))
    )
    (net (code "29") (name "/Output_ch3_1_N") (class "Default")
      (node (ref "R38") (pin "1") (pinfunction "1_1") (pintype "passive"))
      (node (ref "U3") (pin "44") (pinfunction "DC1M_44") (pintype "passive"))
    )
    (net (code "30") (name "/Output_ch3_1_P") (class "Default")
      (node (ref "R38") (pin "2") (pinfunction "2_2") (pintype "passive"))
      (node (ref "U3") (pin "43") (pinfunction "DC1P_43") (pintype "passive"))
    )
    (net (code "31") (name "/Output_ch4_0_N") (class "Default")
      (node (ref "R45") (pin "1") (pinfunction "1_1") (pintype "passive"))
      (node (ref "U3") (pin "42") (pinfunction "DD0M_42") (pintype "passive"))
    )
    (net (code "32") (name "/Output_ch4_0_P") (class "Default")
      (node (ref "R45") (pin "2") (pinfunction "2_2") (pintype "passive"))
      (node (ref "U3") (pin "41") (pinfunction "DD0P_41") (pintype "passive"))
    )
    (net (code "33") (name "/Output_ch4_1_N") (class "Default")
      (node (ref "R46") (pin "1") (pinfunction "1_1") (pintype "passive"))
      (node (ref "U3") (pin "40") (pinfunction "DD1M_40") (pintype "passive"))
    )
    (net (code "34") (name "/Output_ch4_1_P") (class "Default")
      (node (ref "R46") (pin "2") (pinfunction "2_2") (pintype "passive"))
      (node (ref "U3") (pin "39") (pinfunction "DD1P_39") (pintype "passive"))
    )
    (net (code "35") (name "/Reset_ADC") (class "Default")
      (node (ref "U3") (pin "24") (pinfunction "RESET_24") (pintype "passive"))
    )
    (net (code "36") (name "/SCLK") (class "Default")
      (node (ref "U3") (pin "16") (pinfunction "SCLK_16") (pintype "passive"))
    )
    (net (code "37") (name "/SDATA") (class "Default")
      (node (ref "U3") (pin "17") (pinfunction "SDATA_17") (pintype "passive"))
    )
    (net (code "38") (name "/SDOUT") (class "Default")
      (node (ref "U3") (pin "19") (pinfunction "SDOUT_19") (pintype "passive"))
    )
    (net (code "39") (name "/SEN") (class "Default")
      (node (ref "U3") (pin "18") (pinfunction "SEN_18") (pintype "passive"))
    )
    (net (code "40") (name "/Udiff_ch1_N") (class "Default")
      (node (ref "C13") (pin "1") (pinfunction "1_1") (pintype "passive"))
      (node (ref "R25") (pin "2") (pinfunction "2_2") (pintype "passive"))
      (node (ref "U3") (pin "8") (pinfunction "INAM_8") (pintype "passive"))
    )
    (net (code "41") (name "/Udiff_ch1_P") (class "Default")
      (node (ref "C14") (pin "2") (pinfunction "2_2") (pintype "passive"))
      (node (ref "R26") (pin "2") (pinfunction "2_2") (pintype "passive"))
      (node (ref "U3") (pin "9") (pinfunction "INAP_9") (pintype "passive"))
    )
    (net (code "42") (name "/Udiff_ch2+") (class "Default")
      (node (ref "C16") (pin "2") (pinfunction "2_2") (pintype "passive"))
      (node (ref "R28") (pin "2") (pinfunction "2_2") (pintype "passive"))
      (node (ref "U3") (pin "12") (pinfunction "INBP_12") (pintype "passive"))
    )
    (net (code "43") (name "/Udiff_ch2-") (class "Default")
      (node (ref "C15") (pin "1") (pinfunction "1_1") (pintype "passive"))
      (node (ref "R27") (pin "2") (pinfunction "2_2") (pintype "passive"))
      (node (ref "U3") (pin "13") (pinfunction "INBM_13") (pintype "passive"))
    )
    (net (code "44") (name "/Udiff_ch3+") (class "Default")
      (node (ref "C18") (pin "2") (pinfunction "2_2") (pintype "passive"))
      (node (ref "R30") (pin "2") (pinfunction "2_2") (pintype "passive"))
      (node (ref "U3") (pin "31") (pinfunction "INCP_31") (pintype "passive"))
    )
    (net (code "45") (name "/Udiff_ch3-") (class "Default")
      (node (ref "C17") (pin "1") (pinfunction "1_1") (pintype "passive"))
      (node (ref "R29") (pin "2") (pinfunction "2_2") (pintype "passive"))
      (node (ref "U3") (pin "30") (pinfunction "INCM_30") (pintype "passive"))
    )
    (net (code "46") (name "/Udiff_ch4+") (class "Default")
      (node (ref "C20") (pin "2") (pinfunction "2_2") (pintype "passive"))
      (node (ref "R32") (pin "2") (pinfunction "2_2") (pintype "passive"))
      (node (ref "U3") (pin "34") (pinfunction "INDP_34") (pintype "passive"))
    )
    (net (code "47") (name "/Udiff_ch4-") (class "Default")
      (node (ref "C19") (pin "1") (pinfunction "1_1") (pintype "passive"))
      (node (ref "R31") (pin "2") (pinfunction "2_2") (pintype "passive"))
      (node (ref "U3") (pin "35") (pinfunction "INDM_35") (pintype "passive"))
    )
    (net (code "48") (name "/VREF") (class "Default")
      (node (ref "U3") (pin "27") (pinfunction "VCM_27") (pintype "passive"))
      (node (ref "Usup1") (pin "3") (pinfunction "+IN_3") (pintype "input"))
    )
    (net (code "49") (name "GND") (class "Default")
      (node (ref "C1") (pin "1") (pinfunction "1_1") (pintype "passive"))
      (node (ref "C10") (pin "1") (pinfunction "1_1") (pintype "passive"))
      (node (ref "C11") (pin "1") (pinfunction "1_1") (pintype "passive"))
      (node (ref "C12") (pin "1") (pinfunction "1_1") (pintype "passive"))
      (node (ref "C13") (pin "2") (pinfunction "2_2") (pintype "passive"))
      (node (ref "C14") (pin "1") (pinfunction "1_1") (pintype "passive"))
      (node (ref "C15") (pin "2") (pinfunction "2_2") (pintype "passive"))
      (node (ref "C16") (pin "1") (pinfunction "1_1") (pintype "passive"))
      (node (ref "C17") (pin "2") (pinfunction "2_2") (pintype "passive"))
      (node (ref "C18") (pin "1") (pinfunction "1_1") (pintype "passive"))
      (node (ref "C19") (pin "2") (pinfunction "2_2") (pintype "passive"))
      (node (ref "C2") (pin "1") (pinfunction "1_1") (pintype "passive"))
      (node (ref "C20") (pin "1") (pinfunction "1_1") (pintype "passive"))
      (node (ref "C3") (pin "1") (pinfunction "1_1") (pintype "passive"))
      (node (ref "C4") (pin "1") (pinfunction "1_1") (pintype "passive"))
      (node (ref "C5") (pin "1") (pinfunction "1_1") (pintype "passive"))
      (node (ref "C6") (pin "1") (pinfunction "1_1") (pintype "passive"))
      (node (ref "C7") (pin "1") (pinfunction "1_1") (pintype "passive"))
      (node (ref "C8") (pin "1") (pinfunction "1_1") (pintype "passive"))
      (node (ref "C9") (pin "1") (pinfunction "1_1") (pintype "passive"))
      (node (ref "Csh10") (pin "2") (pinfunction "2_2") (pintype "passive"))
      (node (ref "Csh11") (pin "2") (pinfunction "2_2") (pintype "passive"))
      (node (ref "Csh12") (pin "2") (pinfunction "2_2") (pintype "passive"))
      (node (ref "Csh17") (pin "2") (pinfunction "2_2") (pintype "passive"))
      (node (ref "Csh18") (pin "2") (pinfunction "2_2") (pintype "passive"))
      (node (ref "Csh19") (pin "2") (pinfunction "2_2") (pintype "passive"))
      (node (ref "Csh20") (pin "2") (pinfunction "2_2") (pintype "passive"))
      (node (ref "Csh21") (pin "2") (pinfunction "2_2") (pintype "passive"))
      (node (ref "Csh22") (pin "2") (pinfunction "2_2") (pintype "passive"))
      (node (ref "Csh23") (pin "2") (pinfunction "2_2") (pintype "passive"))
      (node (ref "Csh24") (pin "2") (pinfunction "2_2") (pintype "passive"))
      (node (ref "Csh29") (pin "2") (pinfunction "2_2") (pintype "passive"))
      (node (ref "Csh30") (pin "2") (pinfunction "2_2") (pintype "passive"))
      (node (ref "Csh31") (pin "2") (pinfunction "2_2") (pintype "passive"))
      (node (ref "Csh32") (pin "2") (pinfunction "2_2") (pintype "passive"))
      (node (ref "Csh9") (pin "2") (pinfunction "2_2") (pintype "passive"))
      (node (ref "Cu1") (pin "1") (pinfunction "1_1") (pintype "passive"))
      (node (ref "Cu10") (pin "1") (pinfunction "1_1") (pintype "passive"))
      (node (ref "Cu11") (pin "1") (pinfunction "1_1") (pintype "passive"))
      (node (ref "Cu12") (pin "1") (pinfunction "1_1") (pintype "passive"))
      (node (ref "Cu13") (pin "1") (pinfunction "1_1") (pintype "passive"))
      (node (ref "Cu14") (pin "1") (pinfunction "1_1") (pintype "passive"))
      (node (ref "Cu15") (pin "1") (pinfunction "1_1") (pintype "passive"))
      (node (ref "Cu16") (pin "1") (pinfunction "1_1") (pintype "passive"))
      (node (ref "Cu2") (pin "1") (pinfunction "1_1") (pintype "passive"))
      (node (ref "Cu3") (pin "1") (pinfunction "1_1") (pintype "passive"))
      (node (ref "Cu4") (pin "1") (pinfunction "1_1") (pintype "passive"))
      (node (ref "Cu5") (pin "1") (pinfunction "1_1") (pintype "passive"))
      (node (ref "Cu6") (pin "1") (pinfunction "1_1") (pintype "passive"))
      (node (ref "Cu7") (pin "1") (pinfunction "1_1") (pintype "passive"))
      (node (ref "Cu8") (pin "1") (pinfunction "1_1") (pintype "passive"))
      (node (ref "Cu9") (pin "1") (pinfunction "1_1") (pintype "passive"))
      (node (ref "R44") (pin "2") (pinfunction "2_2") (pintype "passive"))
      (node (ref "Rsh13") (pin "2") (pinfunction "2_2") (pintype "passive"))
      (node (ref "Rsh14") (pin "2") (pinfunction "2_2") (pintype "passive"))
      (node (ref "Rsh15") (pin "2") (pinfunction "2_2") (pintype "passive"))
      (node (ref "Rsh16") (pin "2") (pinfunction "2_2") (pintype "passive"))
      (node (ref "Rsh38") (pin "1") (pinfunction "1_1") (pintype "passive"))
      (node (ref "Rsh40") (pin "1") (pinfunction "1_1") (pintype "passive"))
      (node (ref "Rsh42") (pin "1") (pinfunction "1_1") (pintype "passive"))
      (node (ref "Rsh44") (pin "1") (pinfunction "1_1") (pintype "passive"))
      (node (ref "Rsh54") (pin "1") (pinfunction "1_1") (pintype "passive"))
      (node (ref "Rsh56") (pin "1") (pinfunction "1_1") (pintype "passive"))
      (node (ref "Rsh58") (pin "1") (pinfunction "1_1") (pintype "passive"))
      (node (ref "Rsh60") (pin "1") (pinfunction "1_1") (pintype "passive"))
      (node (ref "U1") (pin "25") (pinfunction "Bottom_Pad_25") (pintype "passive"))
      (node (ref "U2") (pin "25") (pinfunction "Bottom_Pad_25") (pintype "passive"))
      (node (ref "U3") (pin "37") (pinfunction "PDN_37") (pintype "passive"))
      (node (ref "Usup1") (pin "2") (pinfunction "E-_2") (pintype "input"))
    )
    (net (code "50") (name "Net-(Csh1-Pad2)") (class "Default")
      (node (ref "Csh1") (pin "2") (pinfunction "2_2") (pintype "passive"))
      (node (ref "Rsh1") (pin "2") (pinfunction "2_2") (pintype "passive"))
      (node (ref "Rsh5") (pin "1") (pinfunction "1_1") (pintype "passive"))
    )
    (net (code "51") (name "Net-(Csh2-Pad2)") (class "Default")
      (node (ref "Csh2") (pin "2") (pinfunction "2_2") (pintype "passive"))
      (node (ref "Rsh1") (pin "1") (pinfunction "1_1") (pintype "passive"))
      (node (ref "Rsh6") (pin "1") (pinfunction "1_1") (pintype "passive"))
    )
    (net (code "52") (name "Net-(Csh3-Pad2)") (class "Default")
      (node (ref "Csh3") (pin "2") (pinfunction "2_2") (pintype "passive"))
      (node (ref "Rsh2") (pin "2") (pinfunction "2_2") (pintype "passive"))
      (node (ref "Rsh7") (pin "1") (pinfunction "1_1") (pintype "passive"))
    )
    (net (code "53") (name "Net-(Csh4-Pad2)") (class "Default")
      (node (ref "Csh4") (pin "2") (pinfunction "2_2") (pintype "passive"))
      (node (ref "Rsh2") (pin "1") (pinfunction "1_1") (pintype "passive"))
      (node (ref "Rsh8") (pin "1") (pinfunction "1_1") (pintype "passive"))
    )
    (net (code "54") (name "Net-(Csh5-Pad2)") (class "Default")
      (node (ref "Csh5") (pin "2") (pinfunction "2_2") (pintype "passive"))
      (node (ref "Rsh3") (pin "2") (pinfunction "2_2") (pintype "passive"))
      (node (ref "Rsh9") (pin "1") (pinfunction "1_1") (pintype "passive"))
    )
    (net (code "55") (name "Net-(Csh6-Pad2)") (class "Default")
      (node (ref "Csh6") (pin "2") (pinfunction "2_2") (pintype "passive"))
      (node (ref "Rsh10") (pin "1") (pinfunction "1_1") (pintype "passive"))
      (node (ref "Rsh3") (pin "1") (pinfunction "1_1") (pintype "passive"))
    )
    (net (code "56") (name "Net-(Csh7-Pad2)") (class "Default")
      (node (ref "Csh7") (pin "2") (pinfunction "2_2") (pintype "passive"))
      (node (ref "Rsh11") (pin "1") (pinfunction "1_1") (pintype "passive"))
      (node (ref "Rsh4") (pin "2") (pinfunction "2_2") (pintype "passive"))
    )
    (net (code "57") (name "Net-(Csh8-Pad2)") (class "Default")
      (node (ref "Csh8") (pin "2") (pinfunction "2_2") (pintype "passive"))
      (node (ref "Rsh12") (pin "1") (pinfunction "1_1") (pintype "passive"))
      (node (ref "Rsh4") (pin "1") (pinfunction "1_1") (pintype "passive"))
    )
    (net (code "58") (name "Net-(Csh13-Pad2)") (class "Default")
      (node (ref "Csh13") (pin "2") (pinfunction "2_2") (pintype "passive"))
      (node (ref "Rsh25") (pin "1") (pinfunction "1_1") (pintype "passive"))
      (node (ref "Rsh29") (pin "1") (pinfunction "1_1") (pintype "passive"))
    )
    (net (code "59") (name "Net-(Csh14-Pad2)") (class "Default")
      (node (ref "Csh14") (pin "2") (pinfunction "2_2") (pintype "passive"))
      (node (ref "Rsh26") (pin "1") (pinfunction "1_1") (pintype "passive"))
      (node (ref "Rsh30") (pin "1") (pinfunction "1_1") (pintype "passive"))
    )
    (net (code "60") (name "Net-(Csh15-Pad2)") (class "Default")
      (node (ref "Csh15") (pin "2") (pinfunction "2_2") (pintype "passive"))
      (node (ref "Rsh27") (pin "1") (pinfunction "1_1") (pintype "passive"))
      (node (ref "Rsh31") (pin "1") (pinfunction "1_1") (pintype "passive"))
    )
    (net (code "61") (name "Net-(Csh16-Pad2)") (class "Default")
      (node (ref "Csh16") (pin "2") (pinfunction "2_2") (pintype "passive"))
      (node (ref "Rsh28") (pin "1") (pinfunction "1_1") (pintype "passive"))
      (node (ref "Rsh32") (pin "1") (pinfunction "1_1") (pintype "passive"))
    )
    (net (code "62") (name "Net-(Csh25-Pad2)") (class "Default")
      (node (ref "Csh25") (pin "2") (pinfunction "2_2") (pintype "passive"))
      (node (ref "Rsh45") (pin "1") (pinfunction "1_1") (pintype "passive"))
      (node (ref "Rsh49") (pin "1") (pinfunction "1_1") (pintype "passive"))
    )
    (net (code "63") (name "Net-(Csh26-Pad2)") (class "Default")
      (node (ref "Csh26") (pin "2") (pinfunction "2_2") (pintype "passive"))
      (node (ref "Rsh46") (pin "1") (pinfunction "1_1") (pintype "passive"))
      (node (ref "Rsh50") (pin "1") (pinfunction "1_1") (pintype "passive"))
    )
    (net (code "64") (name "Net-(Csh27-Pad2)") (class "Default")
      (node (ref "Csh27") (pin "2") (pinfunction "2_2") (pintype "passive"))
      (node (ref "Rsh47") (pin "1") (pinfunction "1_1") (pintype "passive"))
      (node (ref "Rsh51") (pin "1") (pinfunction "1_1") (pintype "passive"))
    )
    (net (code "65") (name "Net-(Csh28-Pad2)") (class "Default")
      (node (ref "Csh28") (pin "2") (pinfunction "2_2") (pintype "passive"))
      (node (ref "Rsh48") (pin "1") (pinfunction "1_1") (pintype "passive"))
      (node (ref "Rsh52") (pin "1") (pinfunction "1_1") (pintype "passive"))
    )
    (net (code "66") (name "Net-(Csh33-Pad2)") (class "Default")
      (node (ref "Csh33") (pin "2") (pinfunction "2_2") (pintype "passive"))
      (node (ref "R5") (pin "1") (pinfunction "1_1") (pintype "passive"))
      (node (ref "R9") (pin "2") (pinfunction "2_2") (pintype "passive"))
    )
    (net (code "67") (name "Net-(Csh34-Pad2)") (class "Default")
      (node (ref "Csh34") (pin "2") (pinfunction "2_2") (pintype "passive"))
      (node (ref "R11") (pin "2") (pinfunction "2_2") (pintype "passive"))
      (node (ref "R6") (pin "1") (pinfunction "1_1") (pintype "passive"))
    )
    (net (code "68") (name "Net-(Csh35-Pad2)") (class "Default")
      (node (ref "Csh35") (pin "2") (pinfunction "2_2") (pintype "passive"))
      (node (ref "R13") (pin "2") (pinfunction "2_2") (pintype "passive"))
      (node (ref "R7") (pin "1") (pinfunction "1_1") (pintype "passive"))
    )
    (net (code "69") (name "Net-(Csh36-Pad2)") (class "Default")
      (node (ref "Csh36") (pin "2") (pinfunction "2_2") (pintype "passive"))
      (node (ref "R15") (pin "2") (pinfunction "2_2") (pintype "passive"))
      (node (ref "R8") (pin "1") (pinfunction "1_1") (pintype "passive"))
    )
    (net (code "70") (name "Net-(U1A-FB1+)") (class "Default")
      (node (ref "R18") (pin "1") (pinfunction "1_1") (pintype "passive"))
      (node (ref "U1") (pin "2") (pinfunction "FB1+_2") (pintype "output"))
    )
    (net (code "71") (name "Net-(U1A-FB1-)") (class "Default")
      (node (ref "R17") (pin "2") (pinfunction "2_2") (pintype "passive"))
      (node (ref "U1") (pin "23") (pinfunction "FB1-_23") (pintype "output"))
    )
    (net (code "72") (name "Net-(U1A-In+)") (class "Default")
      (node (ref "R17") (pin "1") (pinfunction "1_1") (pintype "passive"))
      (node (ref "R9") (pin "1") (pinfunction "1_1") (pintype "passive"))
      (node (ref "U1") (pin "24") (pinfunction "In+_24") (pintype "input"))
    )
    (net (code "73") (name "Net-(U1A-In-)") (class "Default")
      (node (ref "R10") (pin "1") (pinfunction "1_1") (pintype "passive"))
      (node (ref "R18") (pin "2") (pinfunction "2_2") (pintype "passive"))
      (node (ref "U1") (pin "1") (pinfunction "In-_1") (pintype "input"))
    )
    (net (code "74") (name "Net-(U1A-Out+)") (class "Default")
      (node (ref "R26") (pin "1") (pinfunction "1_1") (pintype "passive"))
      (node (ref "U1") (pin "18") (pinfunction "Out+_18") (pintype "output"))
    )
    (net (code "75") (name "Net-(U1A-Out-)") (class "Default")
      (node (ref "R25") (pin "1") (pinfunction "1_1") (pintype "passive"))
      (node (ref "U1") (pin "19") (pinfunction "Out-_19") (pintype "output"))
    )
    (net (code "76") (name "Net-(U1A-Vocm)") (class "Default")
      (node (ref "C5") (pin "2") (pinfunction "2_2") (pintype "passive"))
      (node (ref "C9") (pin "2") (pinfunction "2_2") (pintype "passive"))
      (node (ref "R1") (pin "1") (pinfunction "1_1") (pintype "passive"))
      (node (ref "R10") (pin "2") (pinfunction "2_2") (pintype "passive"))
      (node (ref "U1") (pin "17") (pinfunction "Vocm_17") (pintype "input"))
    )
    (net (code "77") (name "Net-(U1B-FB2+)") (class "Default")
      (node (ref "R20") (pin "1") (pinfunction "1_1") (pintype "passive"))
      (node (ref "U1") (pin "8") (pinfunction "FB2+_8") (pintype "output"))
    )
    (net (code "78") (name "Net-(U1B-FB2-)") (class "Default")
      (node (ref "R19") (pin "2") (pinfunction "2_2") (pintype "passive"))
      (node (ref "U1") (pin "5") (pinfunction "FB2-_5") (pintype "output"))
    )
    (net (code "79") (name "Net-(U1B-In+)") (class "Default")
      (node (ref "R11") (pin "1") (pinfunction "1_1") (pintype "passive"))
      (node (ref "R19") (pin "1") (pinfunction "1_1") (pintype "passive"))
      (node (ref "U1") (pin "6") (pinfunction "In+_6") (pintype "input"))
    )
    (net (code "80") (name "Net-(U1B-In-)") (class "Default")
      (node (ref "R12") (pin "1") (pinfunction "1_1") (pintype "passive"))
      (node (ref "R20") (pin "2") (pinfunction "2_2") (pintype "passive"))
      (node (ref "U1") (pin "7") (pinfunction "In-_7") (pintype "input"))
    )
    (net (code "81") (name "Net-(U1B-Out+)") (class "Default")
      (node (ref "R28") (pin "1") (pinfunction "1_1") (pintype "passive"))
      (node (ref "U1") (pin "12") (pinfunction "Out+_12") (pintype "output"))
    )
    (net (code "82") (name "Net-(U1B-Out-)") (class "Default")
      (node (ref "R27") (pin "1") (pinfunction "1_1") (pintype "passive"))
      (node (ref "U1") (pin "13") (pinfunction "Out-_13") (pintype "output"))
    )
    (net (code "83") (name "Net-(U1B-Vocm)") (class "Default")
      (node (ref "C10") (pin "2") (pinfunction "2_2") (pintype "passive"))
      (node (ref "C6") (pin "2") (pinfunction "2_2") (pintype "passive"))
      (node (ref "R12") (pin "2") (pinfunction "2_2") (pintype "passive"))
      (node (ref "R2") (pin "1") (pinfunction "1_1") (pintype "passive"))
      (node (ref "U1") (pin "11") (pinfunction "Vocm_11") (pintype "input"))
    )
    (net (code "84") (name "Net-(U2A-FB1+)") (class "Default")
      (node (ref "R22") (pin "1") (pinfunction "1_1") (pintype "passive"))
      (node (ref "U2") (pin "2") (pinfunction "FB1+_2") (pintype "output"))
    )
    (net (code "85") (name "Net-(U2A-FB1-)") (class "Default")
      (node (ref "R21") (pin "2") (pinfunction "2_2") (pintype "passive"))
      (node (ref "U2") (pin "23") (pinfunction "FB1-_23") (pintype "output"))
    )
    (net (code "86") (name "Net-(U2A-In+)") (class "Default")
      (node (ref "R13") (pin "1") (pinfunction "1_1") (pintype "passive"))
      (node (ref "R21") (pin "1") (pinfunction "1_1") (pintype "passive"))
      (node (ref "U2") (pin "24") (pinfunction "In+_24") (pintype "input"))
    )
    (net (code "87") (name "Net-(U2A-In-)") (class "Default")
      (node (ref "R14") (pin "1") (pinfunction "1_1") (pintype "passive"))
      (node (ref "R22") (pin "2") (pinfunction "2_2") (pintype "passive"))
      (node (ref "U2") (pin "1") (pinfunction "In-_1") (pintype "input"))
    )
    (net (code "88") (name "Net-(U2A-Out+)") (class "Default")
      (node (ref "R30") (pin "1") (pinfunction "1_1") (pintype "passive"))
      (node (ref "U2") (pin "18") (pinfunction "Out+_18") (pintype "output"))
    )
    (net (code "89") (name "Net-(U2A-Out-)") (class "Default")
      (node (ref "R29") (pin "1") (pinfunction "1_1") (pintype "passive"))
      (node (ref "U2") (pin "19") (pinfunction "Out-_19") (pintype "output"))
    )
    (net (code "90") (name "Net-(U2A-Vocm)") (class "Default")
      (node (ref "C11") (pin "2") (pinfunction "2_2") (pintype "passive"))
      (node (ref "C7") (pin "2") (pinfunction "2_2") (pintype "passive"))
      (node (ref "R14") (pin "2") (pinfunction "2_2") (pintype "passive"))
      (node (ref "R3") (pin "1") (pinfunction "1_1") (pintype "passive"))
      (node (ref "U2") (pin "17") (pinfunction "Vocm_17") (pintype "input"))
    )
    (net (code "91") (name "Net-(U2B-FB2+)") (class "Default")
      (node (ref "R24") (pin "1") (pinfunction "1_1") (pintype "passive"))
      (node (ref "U2") (pin "8") (pinfunction "FB2+_8") (pintype "output"))
    )
    (net (code "92") (name "Net-(U2B-FB2-)") (class "Default")
      (node (ref "R23") (pin "2") (pinfunction "2_2") (pintype "passive"))
      (node (ref "U2") (pin "5") (pinfunction "FB2-_5") (pintype "output"))
    )
    (net (code "93") (name "Net-(U2B-In+)") (class "Default")
      (node (ref "R15") (pin "1") (pinfunction "1_1") (pintype "passive"))
      (node (ref "R23") (pin "1") (pinfunction "1_1") (pintype "passive"))
      (node (ref "U2") (pin "6") (pinfunction "In+_6") (pintype "input"))
    )
    (net (code "94") (name "Net-(U2B-In-)") (class "Default")
      (node (ref "R16") (pin "1") (pinfunction "1_1") (pintype "passive"))
      (node (ref "R24") (pin "2") (pinfunction "2_2") (pintype "passive"))
      (node (ref "U2") (pin "7") (pinfunction "In-_7") (pintype "input"))
    )
    (net (code "95") (name "Net-(U2B-Out+)") (class "Default")
      (node (ref "R32") (pin "1") (pinfunction "1_1") (pintype "passive"))
      (node (ref "U2") (pin "12") (pinfunction "Out+_12") (pintype "output"))
    )
    (net (code "96") (name "Net-(U2B-Out-)") (class "Default")
      (node (ref "R31") (pin "1") (pinfunction "1_1") (pintype "passive"))
      (node (ref "U2") (pin "13") (pinfunction "Out-_13") (pintype "output"))
    )
    (net (code "97") (name "Net-(U2B-Vocm)") (class "Default")
      (node (ref "C12") (pin "2") (pinfunction "2_2") (pintype "passive"))
      (node (ref "C8") (pin "2") (pinfunction "2_2") (pintype "passive"))
      (node (ref "R16") (pin "2") (pinfunction "2_2") (pintype "passive"))
      (node (ref "R4") (pin "1") (pinfunction "1_1") (pintype "passive"))
      (node (ref "U2") (pin "11") (pinfunction "Vocm_11") (pintype "input"))
    )
    (net (code "98") (name "Net-(Ush1-+IN)") (class "Default")
      (node (ref "Rsh13") (pin "1") (pinfunction "1_1") (pintype "passive"))
      (node (ref "Rsh5") (pin "2") (pinfunction "2_2") (pintype "passive"))
      (node (ref "Ush1") (pin "3") (pinfunction "+IN_3") (pintype "input"))
    )
    (net (code "99") (name "Net-(Ush1--IN)") (class "Default")
      (node (ref "Rsh21") (pin "1") (pinfunction "1_1") (pintype "passive"))
      (node (ref "Rsh6") (pin "2") (pinfunction "2_2") (pintype "passive"))
      (node (ref "Ush1") (pin "4") (pinfunction "-IN_4") (pintype "input"))
    )
    (net (code "100") (name "Net-(Ush1-E+)") (class "Default")
      (node (ref "Csh9") (pin "1") (pinfunction "1_1") (pintype "passive"))
      (node (ref "Rsh17") (pin "1") (pinfunction "1_1") (pintype "passive"))
      (node (ref "Ush1") (pin "5") (pinfunction "E+_5") (pintype "input"))
    )
    (net (code "101") (name "Net-(Ush1-OUT)") (class "Default")
      (node (ref "Rsh21") (pin "2") (pinfunction "2_2") (pintype "passive"))
      (node (ref "Rsh25") (pin "2") (pinfunction "2_2") (pintype "passive"))
      (node (ref "Ush1") (pin "1") (pinfunction "OUT_1") (pintype "output"))
    )
    (net (code "102") (name "Net-(Ush2-+IN)") (class "Default")
      (node (ref "Rsh14") (pin "1") (pinfunction "1_1") (pintype "passive"))
      (node (ref "Rsh7") (pin "2") (pinfunction "2_2") (pintype "passive"))
      (node (ref "Ush2") (pin "3") (pinfunction "+IN_3") (pintype "input"))
    )
    (net (code "103") (name "Net-(Ush2--IN)") (class "Default")
      (node (ref "Rsh22") (pin "1") (pinfunction "1_1") (pintype "passive"))
      (node (ref "Rsh8") (pin "2") (pinfunction "2_2") (pintype "passive"))
      (node (ref "Ush2") (pin "4") (pinfunction "-IN_4") (pintype "input"))
    )
    (net (code "104") (name "Net-(Ush2-E+)") (class "Default")
      (node (ref "Csh10") (pin "1") (pinfunction "1_1") (pintype "passive"))
      (node (ref "Rsh18") (pin "1") (pinfunction "1_1") (pintype "passive"))
      (node (ref "Ush2") (pin "5") (pinfunction "E+_5") (pintype "input"))
    )
    (net (code "105") (name "Net-(Ush2-OUT)") (class "Default")
      (node (ref "Rsh22") (pin "2") (pinfunction "2_2") (pintype "passive"))
      (node (ref "Rsh26") (pin "2") (pinfunction "2_2") (pintype "passive"))
      (node (ref "Ush2") (pin "1") (pinfunction "OUT_1") (pintype "output"))
    )
    (net (code "106") (name "Net-(Ush3-+IN)") (class "Default")
      (node (ref "Rsh15") (pin "1") (pinfunction "1_1") (pintype "passive"))
      (node (ref "Rsh9") (pin "2") (pinfunction "2_2") (pintype "passive"))
      (node (ref "Ush3") (pin "3") (pinfunction "+IN_3") (pintype "input"))
    )
    (net (code "107") (name "Net-(Ush3--IN)") (class "Default")
      (node (ref "Rsh10") (pin "2") (pinfunction "2_2") (pintype "passive"))
      (node (ref "Rsh23") (pin "1") (pinfunction "1_1") (pintype "passive"))
      (node (ref "Ush3") (pin "4") (pinfunction "-IN_4") (pintype "input"))
    )
    (net (code "108") (name "Net-(Ush3-E+)") (class "Default")
      (node (ref "Csh11") (pin "1") (pinfunction "1_1") (pintype "passive"))
      (node (ref "Rsh19") (pin "1") (pinfunction "1_1") (pintype "passive"))
      (node (ref "Ush3") (pin "5") (pinfunction "E+_5") (pintype "input"))
    )
    (net (code "109") (name "Net-(Ush3-OUT)") (class "Default")
      (node (ref "Rsh23") (pin "2") (pinfunction "2_2") (pintype "passive"))
      (node (ref "Rsh27") (pin "2") (pinfunction "2_2") (pintype "passive"))
      (node (ref "Ush3") (pin "1") (pinfunction "OUT_1") (pintype "output"))
    )
    (net (code "110") (name "Net-(Ush4-+IN)") (class "Default")
      (node (ref "Rsh11") (pin "2") (pinfunction "2_2") (pintype "passive"))
      (node (ref "Rsh16") (pin "1") (pinfunction "1_1") (pintype "passive"))
      (node (ref "Ush4") (pin "3") (pinfunction "+IN_3") (pintype "input"))
    )
    (net (code "111") (name "Net-(Ush4--IN)") (class "Default")
      (node (ref "Rsh12") (pin "2") (pinfunction "2_2") (pintype "passive"))
      (node (ref "Rsh24") (pin "1") (pinfunction "1_1") (pintype "passive"))
      (node (ref "Ush4") (pin "4") (pinfunction "-IN_4") (pintype "input"))
    )
    (net (code "112") (name "Net-(Ush4-E+)") (class "Default")
      (node (ref "Csh12") (pin "1") (pinfunction "1_1") (pintype "passive"))
      (node (ref "Rsh20") (pin "1") (pinfunction "1_1") (pintype "passive"))
      (node (ref "Ush4") (pin "5") (pinfunction "E+_5") (pintype "input"))
    )
    (net (code "113") (name "Net-(Ush4-OUT)") (class "Default")
      (node (ref "Rsh24") (pin "2") (pinfunction "2_2") (pintype "passive"))
      (node (ref "Rsh28") (pin "2") (pinfunction "2_2") (pintype "passive"))
      (node (ref "Ush4") (pin "1") (pinfunction "OUT_1") (pintype "output"))
    )
    (net (code "114") (name "Net-(Ush5A-+IN)") (class "Default")
      (node (ref "Csh17") (pin "1") (pinfunction "1_1") (pintype "passive"))
      (node (ref "Rsh29") (pin "2") (pinfunction "2_2") (pintype "passive"))
      (node (ref "Ush5") (pin "3") (pinfunction "+IN_3") (pintype "input"))
    )
    (net (code "115") (name "Net-(Ush5A--IN)") (class "Default")
      (node (ref "Rsh37") (pin "1") (pinfunction "1_1") (pintype "passive"))
      (node (ref "Rsh38") (pin "2") (pinfunction "2_2") (pintype "passive"))
      (node (ref "Ush5") (pin "2") (pinfunction "-IN_2") (pintype "input"))
    )
    (net (code "116") (name "Net-(Ush5A-E+)") (class "Default")
      (node (ref "Csh21") (pin "1") (pinfunction "1_1") (pintype "passive"))
      (node (ref "Rsh33") (pin "1") (pinfunction "1_1") (pintype "passive"))
      (node (ref "Ush5") (pin "8") (pinfunction "E+_8") (pintype "input"))
    )
    (net (code "117") (name "Net-(Ush5A-OUT)") (class "Default")
      (node (ref "Csh13") (pin "1") (pinfunction "1_1") (pintype "passive"))
      (node (ref "Rsh37") (pin "2") (pinfunction "2_2") (pintype "passive"))
      (node (ref "Rsh45") (pin "2") (pinfunction "2_2") (pintype "passive"))
      (node (ref "Ush5") (pin "1") (pinfunction "OUT_1") (pintype "output"))
    )
    (net (code "118") (name "Net-(Ush5B-+IN)") (class "Default")
      (node (ref "Csh29") (pin "1") (pinfunction "1_1") (pintype "passive"))
      (node (ref "Rsh49") (pin "2") (pinfunction "2_2") (pintype "passive"))
      (node (ref "Ush5") (pin "5") (pinfunction "+IN_5") (pintype "input"))
    )
    (net (code "119") (name "Net-(Ush5B--IN)") (class "Default")
      (node (ref "Rsh53") (pin "1") (pinfunction "1_1") (pintype "passive"))
      (node (ref "Rsh54") (pin "2") (pinfunction "2_2") (pintype "passive"))
      (node (ref "Ush5") (pin "6") (pinfunction "-IN_6") (pintype "input"))
    )
    (net (code "120") (name "Net-(Ush5B-OUT)") (class "Default")
      (node (ref "Csh25") (pin "1") (pinfunction "1_1") (pintype "passive"))
      (node (ref "Csh33") (pin "1") (pinfunction "1_1") (pintype "passive"))
      (node (ref "Rsh53") (pin "2") (pinfunction "2_2") (pintype "passive"))
      (node (ref "Ush5") (pin "7") (pinfunction "OUT_7") (pintype "output"))
    )
    (net (code "121") (name "Net-(Ush6A-+IN)") (class "Default")
      (node (ref "Csh18") (pin "1") (pinfunction "1_1") (pintype "passive"))
      (node (ref "Rsh30") (pin "2") (pinfunction "2_2") (pintype "passive"))
      (node (ref "Ush6") (pin "3") (pinfunction "+IN_3") (pintype "input"))
    )
    (net (code "122") (name "Net-(Ush6A--IN)") (class "Default")
      (node (ref "Rsh39") (pin "1") (pinfunction "1_1") (pintype "passive"))
      (node (ref "Rsh40") (pin "2") (pinfunction "2_2") (pintype "passive"))
      (node (ref "Ush6") (pin "2") (pinfunction "-IN_2") (pintype "input"))
    )
    (net (code "123") (name "Net-(Ush6A-E+)") (class "Default")
      (node (ref "Csh22") (pin "1") (pinfunction "1_1") (pintype "passive"))
      (node (ref "Rsh34") (pin "1") (pinfunction "1_1") (pintype "passive"))
      (node (ref "Ush6") (pin "8") (pinfunction "E+_8") (pintype "input"))
    )
    (net (code "124") (name "Net-(Ush6A-OUT)") (class "Default")
      (node (ref "Csh14") (pin "1") (pinfunction "1_1") (pintype "passive"))
      (node (ref "Rsh39") (pin "2") (pinfunction "2_2") (pintype "passive"))
      (node (ref "Rsh46") (pin "2") (pinfunction "2_2") (pintype "passive"))
      (node (ref "Ush6") (pin "1") (pinfunction "OUT_1") (pintype "output"))
    )
    (net (code "125") (name "Net-(Ush6B-+IN)") (class "Default")
      (node (ref "Csh30") (pin "1") (pinfunction "1_1") (pintype "passive"))
      (node (ref "Rsh50") (pin "2") (pinfunction "2_2") (pintype "passive"))
      (node (ref "Ush6") (pin "5") (pinfunction "+IN_5") (pintype "input"))
    )
    (net (code "126") (name "Net-(Ush6B--IN)") (class "Default")
      (node (ref "Rsh55") (pin "1") (pinfunction "1_1") (pintype "passive"))
      (node (ref "Rsh56") (pin "2") (pinfunction "2_2") (pintype "passive"))
      (node (ref "Ush6") (pin "6") (pinfunction "-IN_6") (pintype "input"))
    )
    (net (code "127") (name "Net-(Ush6B-OUT)") (class "Default")
      (node (ref "Csh26") (pin "1") (pinfunction "1_1") (pintype "passive"))
      (node (ref "Csh34") (pin "1") (pinfunction "1_1") (pintype "passive"))
      (node (ref "Rsh55") (pin "2") (pinfunction "2_2") (pintype "passive"))
      (node (ref "Ush6") (pin "7") (pinfunction "OUT_7") (pintype "output"))
    )
    (net (code "128") (name "Net-(Ush7A-+IN)") (class "Default")
      (node (ref "Csh19") (pin "1") (pinfunction "1_1") (pintype "passive"))
      (node (ref "Rsh31") (pin "2") (pinfunction "2_2") (pintype "passive"))
      (node (ref "Ush7") (pin "3") (pinfunction "+IN_3") (pintype "input"))
    )
    (net (code "129") (name "Net-(Ush7A--IN)") (class "Default")
      (node (ref "Rsh41") (pin "1") (pinfunction "1_1") (pintype "passive"))
      (node (ref "Rsh42") (pin "2") (pinfunction "2_2") (pintype "passive"))
      (node (ref "Ush7") (pin "2") (pinfunction "-IN_2") (pintype "input"))
    )
    (net (code "130") (name "Net-(Ush7A-E+)") (class "Default")
      (node (ref "Csh23") (pin "1") (pinfunction "1_1") (pintype "passive"))
      (node (ref "Rsh35") (pin "1") (pinfunction "1_1") (pintype "passive"))
      (node (ref "Ush7") (pin "8") (pinfunction "E+_8") (pintype "input"))
    )
    (net (code "131") (name "Net-(Ush7A-OUT)") (class "Default")
      (node (ref "Csh15") (pin "1") (pinfunction "1_1") (pintype "passive"))
      (node (ref "Rsh41") (pin "2") (pinfunction "2_2") (pintype "passive"))
      (node (ref "Rsh47") (pin "2") (pinfunction "2_2") (pintype "passive"))
      (node (ref "Ush7") (pin "1") (pinfunction "OUT_1") (pintype "output"))
    )
    (net (code "132") (name "Net-(Ush7B-+IN)") (class "Default")
      (node (ref "Csh31") (pin "1") (pinfunction "1_1") (pintype "passive"))
      (node (ref "Rsh51") (pin "2") (pinfunction "2_2") (pintype "passive"))
      (node (ref "Ush7") (pin "5") (pinfunction "+IN_5") (pintype "input"))
    )
    (net (code "133") (name "Net-(Ush7B--IN)") (class "Default")
      (node (ref "Rsh57") (pin "1") (pinfunction "1_1") (pintype "passive"))
      (node (ref "Rsh58") (pin "2") (pinfunction "2_2") (pintype "passive"))
      (node (ref "Ush7") (pin "6") (pinfunction "-IN_6") (pintype "input"))
    )
    (net (code "134") (name "Net-(Ush7B-OUT)") (class "Default")
      (node (ref "Csh27") (pin "1") (pinfunction "1_1") (pintype "passive"))
      (node (ref "Csh35") (pin "1") (pinfunction "1_1") (pintype "passive"))
      (node (ref "Rsh57") (pin "2") (pinfunction "2_2") (pintype "passive"))
      (node (ref "Ush7") (pin "7") (pinfunction "OUT_7") (pintype "output"))
    )
    (net (code "135") (name "Net-(Ush8A-+IN)") (class "Default")
      (node (ref "Csh20") (pin "1") (pinfunction "1_1") (pintype "passive"))
      (node (ref "Rsh32") (pin "2") (pinfunction "2_2") (pintype "passive"))
      (node (ref "Ush8") (pin "3") (pinfunction "+IN_3") (pintype "input"))
    )
    (net (code "136") (name "Net-(Ush8A--IN)") (class "Default")
      (node (ref "Rsh43") (pin "1") (pinfunction "1_1") (pintype "passive"))
      (node (ref "Rsh44") (pin "2") (pinfunction "2_2") (pintype "passive"))
      (node (ref "Ush8") (pin "2") (pinfunction "-IN_2") (pintype "input"))
    )
    (net (code "137") (name "Net-(Ush8A-E+)") (class "Default")
      (node (ref "Csh24") (pin "1") (pinfunction "1_1") (pintype "passive"))
      (node (ref "Rsh36") (pin "1") (pinfunction "1_1") (pintype "passive"))
      (node (ref "Ush8") (pin "8") (pinfunction "E+_8") (pintype "input"))
    )
    (net (code "138") (name "Net-(Ush8A-OUT)") (class "Default")
      (node (ref "Csh16") (pin "1") (pinfunction "1_1") (pintype "passive"))
      (node (ref "Rsh43") (pin "2") (pinfunction "2_2") (pintype "passive"))
      (node (ref "Rsh48") (pin "2") (pinfunction "2_2") (pintype "passive"))
      (node (ref "Ush8") (pin "1") (pinfunction "OUT_1") (pintype "output"))
    )
    (net (code "139") (name "Net-(Ush8B-+IN)") (class "Default")
      (node (ref "Csh32") (pin "1") (pinfunction "1_1") (pintype "passive"))
      (node (ref "Rsh52") (pin "2") (pinfunction "2_2") (pintype "passive"))
      (node (ref "Ush8") (pin "5") (pinfunction "+IN_5") (pintype "input"))
    )
    (net (code "140") (name "Net-(Ush8B--IN)") (class "Default")
      (node (ref "Rsh59") (pin "1") (pinfunction "1_1") (pintype "passive"))
      (node (ref "Rsh60") (pin "2") (pinfunction "2_2") (pintype "passive"))
      (node (ref "Ush8") (pin "6") (pinfunction "-IN_6") (pintype "input"))
    )
    (net (code "141") (name "Net-(Ush8B-OUT)") (class "Default")
      (node (ref "Csh28") (pin "1") (pinfunction "1_1") (pintype "passive"))
      (node (ref "Csh36") (pin "1") (pinfunction "1_1") (pintype "passive"))
      (node (ref "Rsh59") (pin "2") (pinfunction "2_2") (pintype "passive"))
      (node (ref "Ush8") (pin "7") (pinfunction "OUT_7") (pintype "output"))
    )
    (net (code "142") (name "Net-(Usup1--IN)") (class "Default")
      (node (ref "C21") (pin "2") (pinfunction "2_2") (pintype "passive"))
      (node (ref "R42") (pin "1") (pinfunction "1_1") (pintype "passive"))
      (node (ref "Usup1") (pin "4") (pinfunction "-IN_4") (pintype "input"))
    )
    (net (code "143") (name "Net-(Usup1-OUT)") (class "Default")
      (node (ref "C21") (pin "1") (pinfunction "1_1") (pintype "passive"))
      (node (ref "R41") (pin "1") (pinfunction "1_1") (pintype "passive"))
      (node (ref "Usup1") (pin "1") (pinfunction "OUT_1") (pintype "output"))
    )
    (net (code "144") (name "VOffset+") (class "Default")
      (node (ref "C1") (pin "2") (pinfunction "2_2") (pintype "passive"))
      (node (ref "C2") (pin "2") (pinfunction "2_2") (pintype "passive"))
      (node (ref "C3") (pin "2") (pinfunction "2_2") (pintype "passive"))
      (node (ref "C4") (pin "2") (pinfunction "2_2") (pintype "passive"))
      (node (ref "R43") (pin "2") (pinfunction "2_2") (pintype "passive"))
      (node (ref "R44") (pin "1") (pinfunction "1_1") (pintype "passive"))
      (node (ref "R5") (pin "2") (pinfunction "2_2") (pintype "passive"))
      (node (ref "R6") (pin "2") (pinfunction "2_2") (pintype "passive"))
      (node (ref "R7") (pin "2") (pinfunction "2_2") (pintype "passive"))
      (node (ref "R8") (pin "2") (pinfunction "2_2") (pintype "passive"))
    )
    (net (code "145") (name "Vcm") (class "Default")
      (node (ref "R1") (pin "2") (pinfunction "2_2") (pintype "passive"))
      (node (ref "R2") (pin "2") (pinfunction "2_2") (pintype "passive"))
      (node (ref "R3") (pin "2") (pinfunction "2_2") (pintype "passive"))
      (node (ref "R4") (pin "2") (pinfunction "2_2") (pintype "passive"))
      (node (ref "R41") (pin "2") (pinfunction "2_2") (pintype "passive"))
      (node (ref "R42") (pin "2") (pinfunction "2_2") (pintype "passive"))
      (node (ref "R43") (pin "1") (pinfunction "1_1") (pintype "passive"))
    )
    (net (code "146") (name "unconnected-(U1C-PD1-Pad20)") (class "Default")
      (node (ref "U1") (pin "20") (pinfunction "PD1_20") (pintype "passive"))
    )
    (net (code "147") (name "unconnected-(U1C-PD2-Pad14)") (class "Default")
      (node (ref "U1") (pin "14") (pinfunction "PD2_14") (pintype "passive"))
    )
    (net (code "148") (name "unconnected-(U2C-PD1-Pad20)") (class "Default")
      (node (ref "U2") (pin "20") (pinfunction "PD1_20") (pintype "passive"))
    )
    (net (code "149") (name "unconnected-(U2C-PD2-Pad14)") (class "Default")
      (node (ref "U2") (pin "14") (pinfunction "PD2_14") (pintype "passive"))
    )
    (net (code "150") (name "unconnected-(U3-SYSREFM-Pad26)") (class "Default")
      (node (ref "U3") (pin "26") (pinfunction "SYSREFM_26") (pintype "passive"))
    )
    (net (code "151") (name "unconnected-(U3-SYSREFP-Pad25)") (class "Default")
      (node (ref "U3") (pin "25") (pinfunction "SYSREFP_25") (pintype "passive"))
    )
    (net (code "152") (name "unconnected-(Ush5B-E+-Pad8)") (class "Default")
      (node (ref "Ush5") (pin "8") (pinfunction "E+_8") (pintype "input"))
    )
    (net (code "153") (name "unconnected-(Ush5B-E--Pad4)") (class "Default")
      (node (ref "Ush5") (pin "4") (pinfunction "E-_4") (pintype "input"))
    )
    (net (code "154") (name "unconnected-(Ush6B-E+-Pad8)") (class "Default")
      (node (ref "Ush6") (pin "8") (pinfunction "E+_8") (pintype "input"))
    )
    (net (code "155") (name "unconnected-(Ush6B-E--Pad4)") (class "Default")
      (node (ref "Ush6") (pin "4") (pinfunction "E-_4") (pintype "input"))
    )
    (net (code "156") (name "unconnected-(Ush7B-E+-Pad8)") (class "Default")
      (node (ref "Ush7") (pin "8") (pinfunction "E+_8") (pintype "input"))
    )
    (net (code "157") (name "unconnected-(Ush7B-E--Pad4)") (class "Default")
      (node (ref "Ush7") (pin "4") (pinfunction "E-_4") (pintype "input"))
    )
    (net (code "158") (name "unconnected-(Ush8B-E+-Pad8)") (class "Default")
      (node (ref "Ush8") (pin "8") (pinfunction "E+_8") (pintype "input"))
    )
    (net (code "159") (name "unconnected-(Ush8B-E--Pad4)") (class "Default")
      (node (ref "Ush8") (pin "4") (pinfunction "E-_4") (pintype "input"))
    )
  )
)
